# SAE_Shifter_Schem.net
KiCad netlist of a schematic drawn in EAGLE
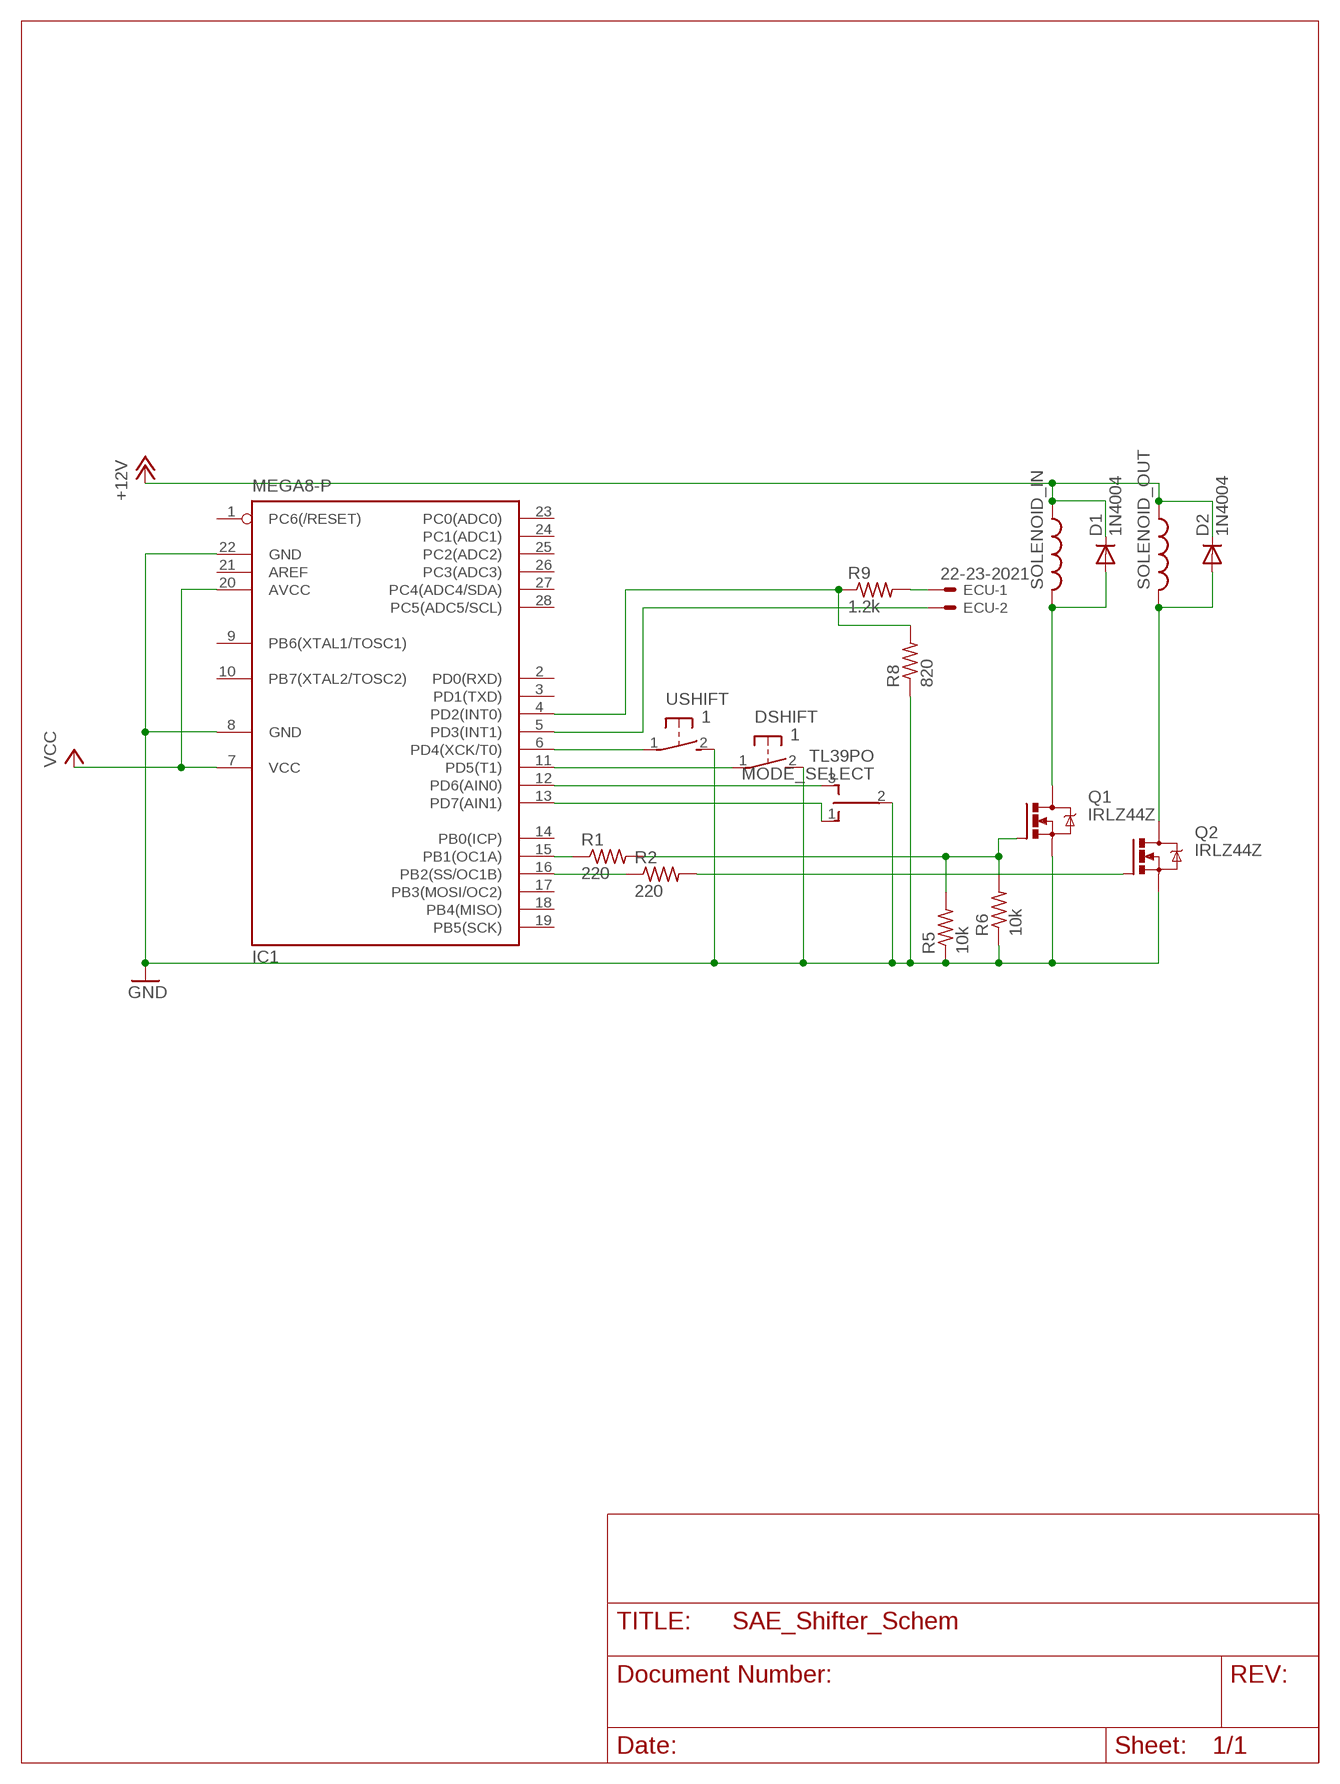
[diagram p0: schematic, sheet 1]

(export (version "E")
  (design (tool "Eeschema 10.0.6"))
  (components
    (comp (ref "D1")
      (value "1N4004")
      (footprint "eagle-import:DO41-10")
      (libsource (lib "eagle-import") (part "1N4004"))
    )
    (comp (ref "D2")
      (value "1N4004")
      (footprint "eagle-import:DO41-10")
      (libsource (lib "eagle-import") (part "1N4004"))
    )
    (comp (ref "DSHIFT")
      (value "1")
      (footprint "eagle-import:B3F-31XX")
      (fields (field (name "MPN") "B3F-3100"))
      (libsource (lib "eagle-import") (part "31-XX"))
    )
    (comp (ref "ECU")
      (value "22-23-2021")
      (footprint "eagle-import:22-23-2021")
      (fields (field (name "MF") "MOLEX"))
      (libsource (lib "eagle-import") (part "22-23-2021"))
    )
    (comp (ref "IC1")
      (value "MEGA8-P")
      (footprint "eagle-import:DIL28-3")
      (libsource (lib "eagle-import") (part "MEGA8-P"))
    )
    (comp (ref "MODE_SELECT")
      (value "TL39PO")
      (footprint "eagle-import:TL3XPO")
      (libsource (lib "eagle-import") (part "TL39PO"))
    )
    (comp (ref "Q1")
      (value "IRLZ44Z")
      (footprint "eagle-import:TO220BH")
      (libsource (lib "eagle-import") (part "IRLZ44Z"))
    )
    (comp (ref "Q2")
      (value "IRLZ44Z")
      (footprint "eagle-import:TO220BH")
      (libsource (lib "eagle-import") (part "IRLZ44Z"))
    )
    (comp (ref "R1")
      (value "220")
      (footprint "eagle-import:0207_10")
      (libsource (lib "eagle-import") (part "R-US_0207/10"))
    )
    (comp (ref "R2")
      (value "220")
      (footprint "eagle-import:0207_10")
      (libsource (lib "eagle-import") (part "R-US_0207/10"))
    )
    (comp (ref "R5")
      (value "10k")
      (footprint "eagle-import:0207_10")
      (libsource (lib "eagle-import") (part "R-US_0207/10"))
    )
    (comp (ref "R6")
      (value "10k")
      (footprint "eagle-import:0207_10")
      (libsource (lib "eagle-import") (part "R-US_0207/10"))
    )
    (comp (ref "R8")
      (value "820")
      (footprint "eagle-import:0207_10")
      (libsource (lib "eagle-import") (part "R-US_0207/10"))
    )
    (comp (ref "R9")
      (value "1.2k")
      (footprint "eagle-import:0207_10")
      (libsource (lib "eagle-import") (part "R-US_0207/10"))
    )
    (comp (ref "SOLENOID_IN")
      (value "L-US0207/10")
      (footprint "eagle-import:0207_10")
      (libsource (lib "eagle-import") (part "L-US0207/10"))
    )
    (comp (ref "SOLENOID_OUT")
      (value "L-US0207/10")
      (footprint "eagle-import:0207_10")
      (libsource (lib "eagle-import") (part "L-US0207/10"))
    )
    (comp (ref "USHIFT")
      (value "1")
      (footprint "eagle-import:B3F-31XX")
      (fields (field (name "MPN") "B3F-3100"))
      (libsource (lib "eagle-import") (part "31-XX"))
    )
  )
  (nets
    (net (code "1") (name "+12V") (class "Default")
      (node (ref "D1") (pin "C") (pinfunction "C_C") (pintype "passive"))
      (node (ref "D2") (pin "C") (pinfunction "C_C") (pintype "passive"))
      (node (ref "SOLENOID_IN") (pin "1") (pinfunction "1_1") (pintype "passive"))
      (node (ref "SOLENOID_OUT") (pin "1") (pinfunction "1_1") (pintype "passive"))
    )
    (net (code "2") (name "GND") (class "Default")
      (node (ref "DSHIFT") (pin "2") (pinfunction "S_2") (pintype "passive"))
      (node (ref "IC1") (pin "22") (pinfunction "GND_22") (pintype "power_in"))
      (node (ref "IC1") (pin "8") (pinfunction "GND_8") (pintype "power_in"))
      (node (ref "MODE_SELECT") (pin "2") (pinfunction "P_2") (pintype "passive"))
      (node (ref "Q1") (pin "S") (pinfunction "S_S") (pintype "passive"))
      (node (ref "Q2") (pin "S") (pinfunction "S_S") (pintype "passive"))
      (node (ref "R5") (pin "1") (pinfunction "1_1") (pintype "passive"))
      (node (ref "R6") (pin "1") (pinfunction "1_1") (pintype "passive"))
      (node (ref "R8") (pin "1") (pinfunction "1_1") (pintype "passive"))
      (node (ref "USHIFT") (pin "2") (pinfunction "S_2") (pintype "passive"))
    )
    (net (code "3") (name "Net-(D1-PadA)") (class "Default")
      (node (ref "D1") (pin "A") (pinfunction "A_A") (pintype "passive"))
      (node (ref "Q1") (pin "D") (pinfunction "D_D") (pintype "passive"))
      (node (ref "SOLENOID_IN") (pin "2") (pinfunction "2_2") (pintype "passive"))
    )
    (net (code "4") (name "Net-(D2-PadA)") (class "Default")
      (node (ref "D2") (pin "A") (pinfunction "A_A") (pintype "passive"))
      (node (ref "Q2") (pin "D") (pinfunction "D_D") (pintype "passive"))
      (node (ref "SOLENOID_OUT") (pin "2") (pinfunction "2_2") (pintype "passive"))
    )
    (net (code "5") (name "Net-(DSHIFT-P)") (class "Default")
      (node (ref "DSHIFT") (pin "1") (pinfunction "P_1") (pintype "passive"))
      (node (ref "IC1") (pin "11") (pinfunction "PD5(T1)_11") (pintype "bidirectional"))
    )
    (net (code "6") (name "Net-(ECUA-S)") (class "Default")
      (node (ref "ECU") (pin "1") (pinfunction "S_1") (pintype "passive"))
      (node (ref "R9") (pin "2") (pinfunction "2_2") (pintype "passive"))
    )
    (net (code "7") (name "Net-(ECUB-S)") (class "Default")
      (node (ref "ECU") (pin "2") (pinfunction "S_2") (pintype "passive"))
      (node (ref "IC1") (pin "5") (pinfunction "PD3(INT1)_5") (pintype "bidirectional"))
    )
    (net (code "8") (name "Net-(IC1-PB1(OC1A))") (class "Default")
      (node (ref "IC1") (pin "15") (pinfunction "PB1(OC1A)_15") (pintype "bidirectional"))
      (node (ref "R1") (pin "1") (pinfunction "1_1") (pintype "passive"))
    )
    (net (code "9") (name "Net-(IC1-PB2(SS{slash}OC1B))") (class "Default")
      (node (ref "IC1") (pin "16") (pinfunction "PB2(SS/OC1B)_16") (pintype "bidirectional"))
      (node (ref "R2") (pin "1") (pinfunction "1_1") (pintype "passive"))
    )
    (net (code "10") (name "Net-(IC1-PD2(INT0))") (class "Default")
      (node (ref "IC1") (pin "4") (pinfunction "PD2(INT0)_4") (pintype "bidirectional"))
      (node (ref "R8") (pin "2") (pinfunction "2_2") (pintype "passive"))
      (node (ref "R9") (pin "1") (pinfunction "1_1") (pintype "passive"))
    )
    (net (code "11") (name "Net-(IC1-PD4(XCK{slash}T0))") (class "Default")
      (node (ref "IC1") (pin "6") (pinfunction "PD4(XCK/T0)_6") (pintype "bidirectional"))
      (node (ref "USHIFT") (pin "1") (pinfunction "P_1") (pintype "passive"))
    )
    (net (code "12") (name "Net-(IC1-PD6(AIN0))") (class "Default")
      (node (ref "IC1") (pin "12") (pinfunction "PD6(AIN0)_12") (pintype "bidirectional"))
      (node (ref "MODE_SELECT") (pin "3") (pinfunction "S_3") (pintype "passive"))
    )
    (net (code "13") (name "Net-(IC1-PD7(AIN1))") (class "Default")
      (node (ref "IC1") (pin "13") (pinfunction "PD7(AIN1)_13") (pintype "bidirectional"))
      (node (ref "MODE_SELECT") (pin "1") (pinfunction "O_1") (pintype "passive"))
    )
    (net (code "14") (name "Net-(Q1-PadG)") (class "Default")
      (node (ref "Q1") (pin "G") (pinfunction "G_G") (pintype "passive"))
      (node (ref "R1") (pin "2") (pinfunction "2_2") (pintype "passive"))
      (node (ref "R5") (pin "2") (pinfunction "2_2") (pintype "passive"))
      (node (ref "R6") (pin "2") (pinfunction "2_2") (pintype "passive"))
    )
    (net (code "15") (name "Net-(Q2-PadG)") (class "Default")
      (node (ref "Q2") (pin "G") (pinfunction "G_G") (pintype "passive"))
      (node (ref "R2") (pin "2") (pinfunction "2_2") (pintype "passive"))
    )
    (net (code "16") (name "VCC") (class "Default")
      (node (ref "IC1") (pin "20") (pinfunction "AVCC_20") (pintype "power_in"))
      (node (ref "IC1") (pin "7") (pinfunction "VCC_7") (pintype "power_in"))
    )
    (net (code "17") (name "unconnected-(IC1-AREF-Pad21)") (class "Default")
      (node (ref "IC1") (pin "21") (pinfunction "AREF_21") (pintype "passive"))
    )
    (net (code "18") (name "unconnected-(IC1-PB0(ICP)-Pad14)") (class "Default")
      (node (ref "IC1") (pin "14") (pinfunction "PB0(ICP)_14") (pintype "bidirectional"))
    )
    (net (code "19") (name "unconnected-(IC1-PB3(MOSI{slash}OC2)-Pad17)") (class "Default")
      (node (ref "IC1") (pin "17") (pinfunction "PB3(MOSI/OC2)_17") (pintype "bidirectional"))
    )
    (net (code "20") (name "unconnected-(IC1-PB4(MISO)-Pad18)") (class "Default")
      (node (ref "IC1") (pin "18") (pinfunction "PB4(MISO)_18") (pintype "bidirectional"))
    )
    (net (code "21") (name "unconnected-(IC1-PB5(SCK)-Pad19)") (class "Default")
      (node (ref "IC1") (pin "19") (pinfunction "PB5(SCK)_19") (pintype "bidirectional"))
    )
    (net (code "22") (name "unconnected-(IC1-PB6(XTAL1{slash}TOSC1)-Pad9)") (class "Default")
      (node (ref "IC1") (pin "9") (pinfunction "PB6(XTAL1/TOSC1)_9") (pintype "bidirectional"))
    )
    (net (code "23") (name "unconnected-(IC1-PB7(XTAL2{slash}TOSC2)-Pad10)") (class "Default")
      (node (ref "IC1") (pin "10") (pinfunction "PB7(XTAL2/TOSC2)_10") (pintype "bidirectional"))
    )
    (net (code "24") (name "unconnected-(IC1-PC0(ADC0)-Pad23)") (class "Default")
      (node (ref "IC1") (pin "23") (pinfunction "PC0(ADC0)_23") (pintype "bidirectional"))
    )
    (net (code "25") (name "unconnected-(IC1-PC1(ADC1)-Pad24)") (class "Default")
      (node (ref "IC1") (pin "24") (pinfunction "PC1(ADC1)_24") (pintype "bidirectional"))
    )
    (net (code "26") (name "unconnected-(IC1-PC2(ADC2)-Pad25)") (class "Default")
      (node (ref "IC1") (pin "25") (pinfunction "PC2(ADC2)_25") (pintype "bidirectional"))
    )
    (net (code "27") (name "unconnected-(IC1-PC3(ADC3)-Pad26)") (class "Default")
      (node (ref "IC1") (pin "26") (pinfunction "PC3(ADC3)_26") (pintype "bidirectional"))
    )
    (net (code "28") (name "unconnected-(IC1-PC4(ADC4{slash}SDA)-Pad27)") (class "Default")
      (node (ref "IC1") (pin "27") (pinfunction "PC4(ADC4/SDA)_27") (pintype "bidirectional"))
    )
    (net (code "29") (name "unconnected-(IC1-PC5(ADC5{slash}SCL)-Pad28)") (class "Default")
      (node (ref "IC1") (pin "28") (pinfunction "PC5(ADC5/SCL)_28") (pintype "bidirectional"))
    )
    (net (code "30") (name "unconnected-(IC1-PC6({slash}RESET)-Pad1)") (class "Default")
      (node (ref "IC1") (pin "1") (pinfunction "PC6(/RESET)_1") (pintype "bidirectional"))
    )
    (net (code "31") (name "unconnected-(IC1-PD0(RXD)-Pad2)") (class "Default")
      (node (ref "IC1") (pin "2") (pinfunction "PD0(RXD)_2") (pintype "bidirectional"))
    )
    (net (code "32") (name "unconnected-(IC1-PD1(TXD)-Pad3)") (class "Default")
      (node (ref "IC1") (pin "3") (pinfunction "PD1(TXD)_3") (pintype "bidirectional"))
    )
  )
)
